# bolid-iso-motor-control.net
KiCad netlist of a schematic drawn in Altium Designer
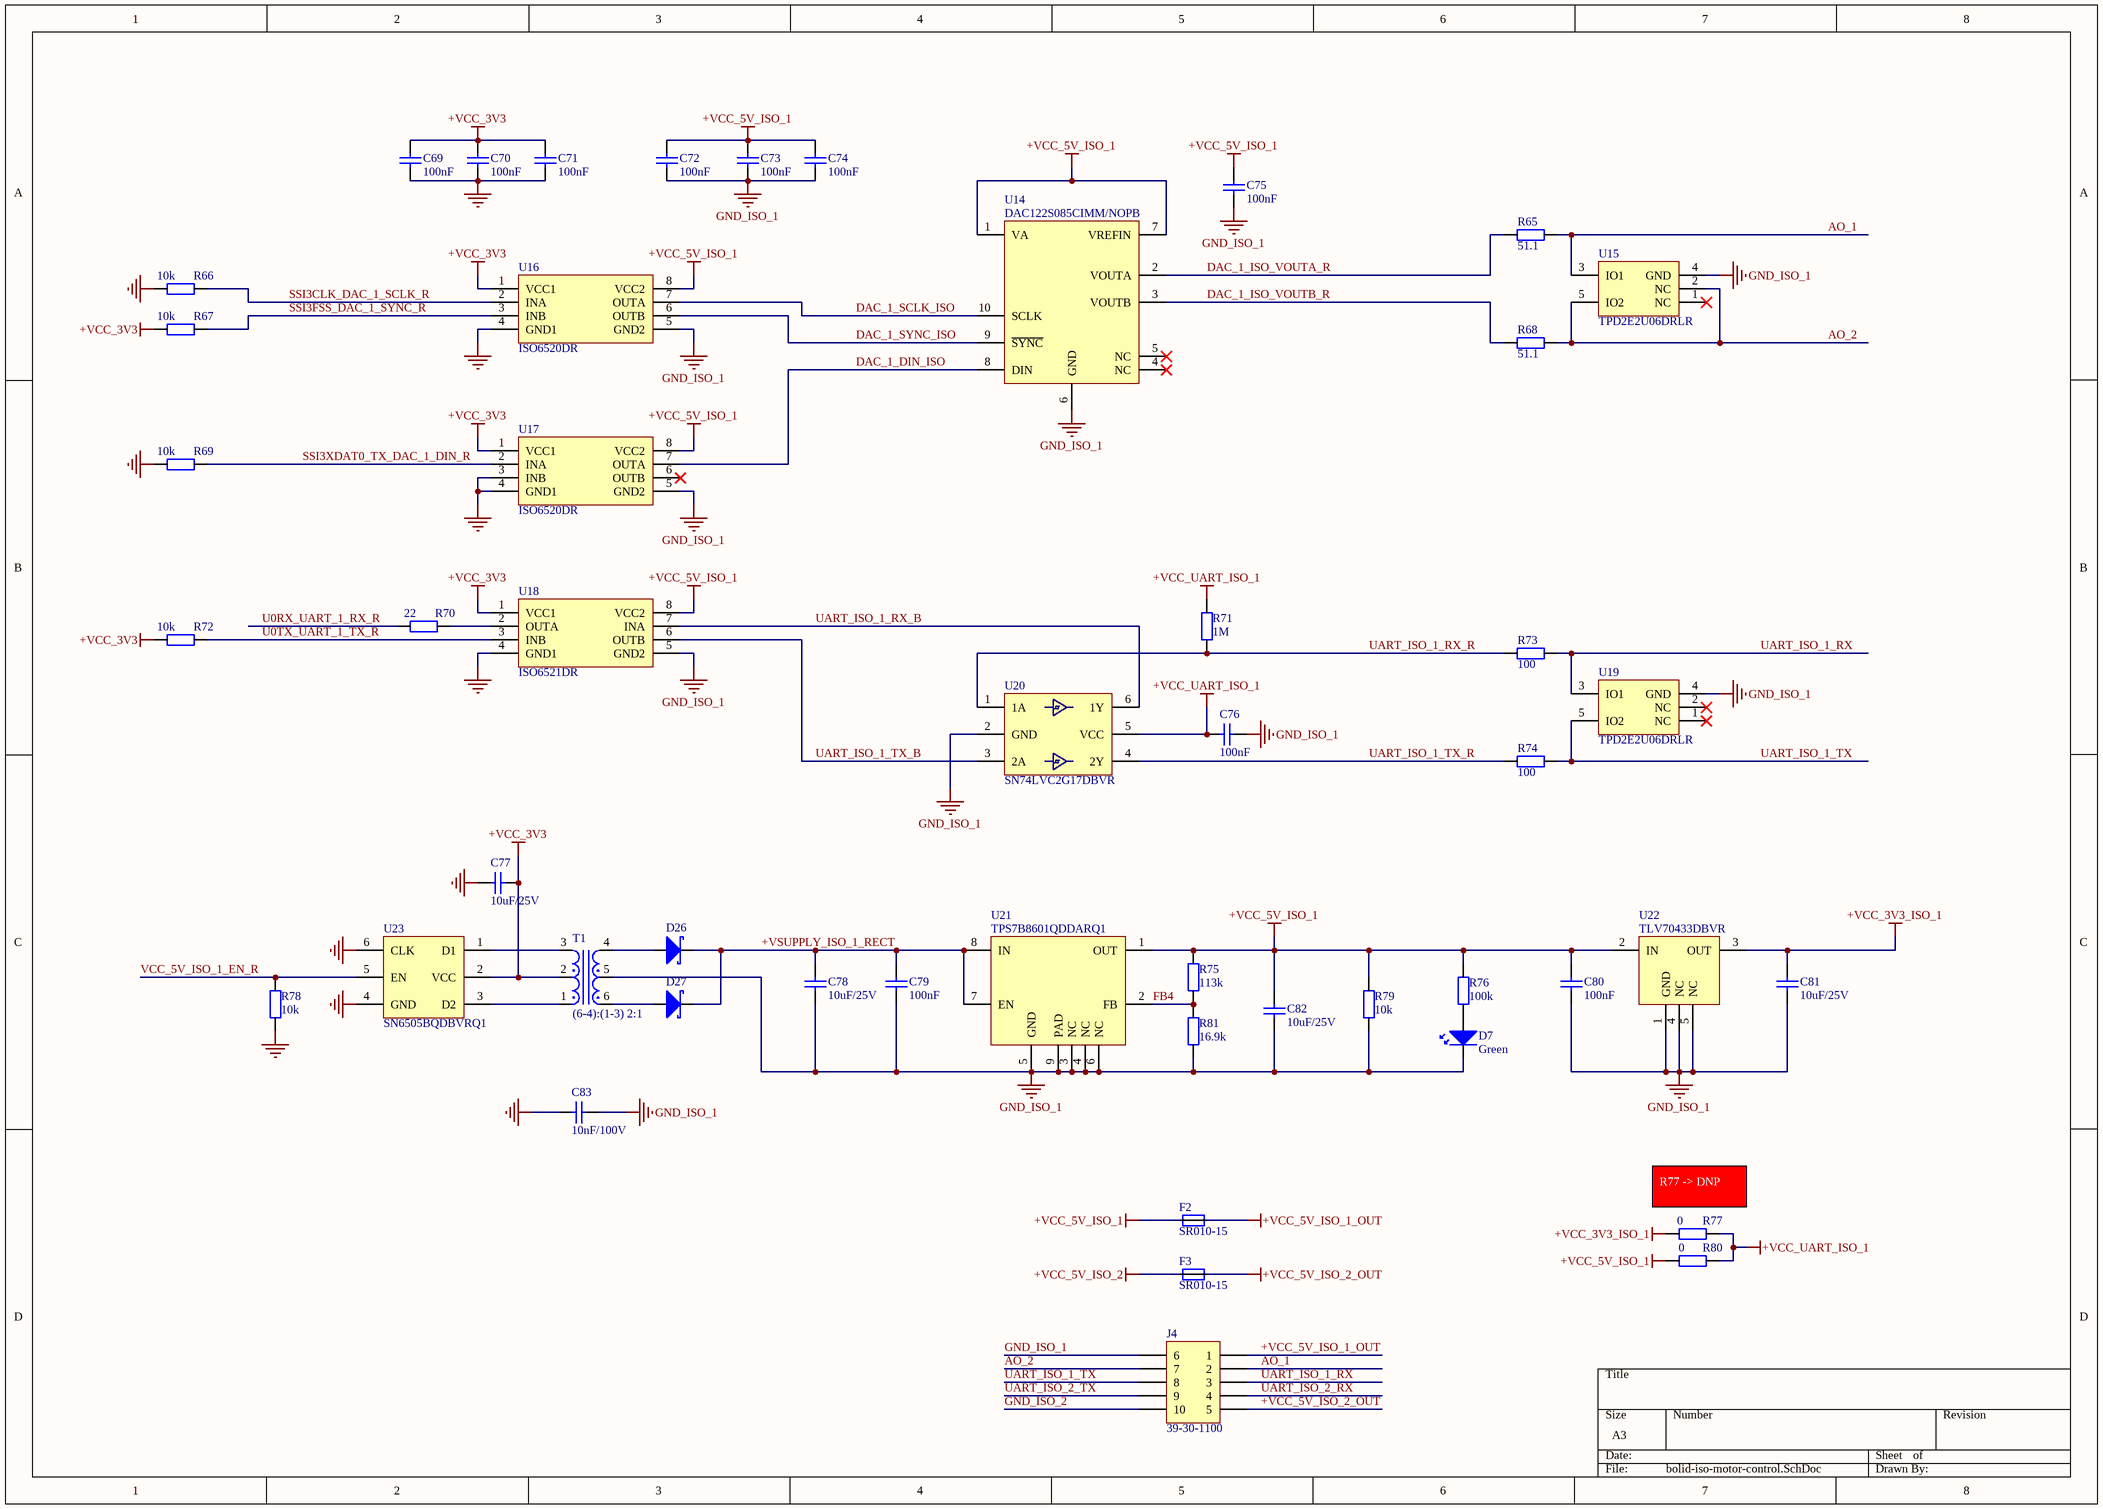
[diagram p0: bolid-iso-motor-control.SchDoc]

(export (version "E")
  (design (tool "Eeschema 10.0.6"))
  (components
    (comp (ref "C69")
      (value "GRM155R71H104KE14D")
      (footprint "C0402-CAPC100X50X55L22 - Tayio Yuden TDK")
      (description "MLCC 0402 (1005) 100nF 10% 50V X7R")
      (fields
        (field (name "MANUFACTURER") "Murata Electronics")
        (field (name "TOLERANCE") "10 %")
        (field (name "VALUE DISPLAYED") "100nF")
      )
      (libsource (lib "capacitors2") (part "GRM155R71H104KE14D"))
    )
    (comp (ref "C70")
      (value "GRM155R71H104KE14D")
      (footprint "C0402-CAPC100X50X55L22 - Tayio Yuden TDK")
      (description "MLCC 0402 (1005) 100nF 10% 50V X7R")
      (fields
        (field (name "MANUFACTURER") "Murata Electronics")
        (field (name "TOLERANCE") "10 %")
        (field (name "VALUE DISPLAYED") "100nF")
      )
      (libsource (lib "capacitors2") (part "GRM155R71H104KE14D"))
    )
    (comp (ref "C71")
      (value "GRM155R71H104KE14D")
      (footprint "C0402-CAPC100X50X55L22 - Tayio Yuden TDK")
      (description "MLCC 0402 (1005) 100nF 10% 50V X7R")
      (fields
        (field (name "MANUFACTURER") "Murata Electronics")
        (field (name "TOLERANCE") "10 %")
        (field (name "VALUE DISPLAYED") "100nF")
      )
      (libsource (lib "capacitors2") (part "GRM155R71H104KE14D"))
    )
    (comp (ref "C72")
      (value "GRM155R71H104KE14D")
      (footprint "C0402-CAPC100X50X55L22 - Tayio Yuden TDK")
      (description "MLCC 0402 (1005) 100nF 10% 50V X7R")
      (fields
        (field (name "MANUFACTURER") "Murata Electronics")
        (field (name "TOLERANCE") "10 %")
        (field (name "VALUE DISPLAYED") "100nF")
      )
      (libsource (lib "capacitors2") (part "GRM155R71H104KE14D"))
    )
    (comp (ref "C73")
      (value "GRM155R71H104KE14D")
      (footprint "C0402-CAPC100X50X55L22 - Tayio Yuden TDK")
      (description "MLCC 0402 (1005) 100nF 10% 50V X7R")
      (fields
        (field (name "MANUFACTURER") "Murata Electronics")
        (field (name "TOLERANCE") "10 %")
        (field (name "VALUE DISPLAYED") "100nF")
      )
      (libsource (lib "capacitors2") (part "GRM155R71H104KE14D"))
    )
    (comp (ref "C74")
      (value "GRM155R71H104KE14D")
      (footprint "C0402-CAPC100X50X55L22 - Tayio Yuden TDK")
      (description "MLCC 0402 (1005) 100nF 10% 50V X7R")
      (fields
        (field (name "MANUFACTURER") "Murata Electronics")
        (field (name "TOLERANCE") "10 %")
        (field (name "VALUE DISPLAYED") "100nF")
      )
      (libsource (lib "capacitors2") (part "GRM155R71H104KE14D"))
    )
    (comp (ref "C75")
      (value "GRM155R71H104KE14D")
      (footprint "C0402-CAPC100X50X55L22 - Tayio Yuden TDK")
      (description "MLCC 0402 (1005) 100nF 10% 50V X7R")
      (fields
        (field (name "MANUFACTURER") "Murata Electronics")
        (field (name "TOLERANCE") "10 %")
        (field (name "VALUE DISPLAYED") "100nF")
      )
      (libsource (lib "capacitors2") (part "GRM155R71H104KE14D"))
    )
    (comp (ref "C76")
      (value "GRM155R71H104KE14D")
      (footprint "C0402-CAPC100X50X55L22 - Tayio Yuden TDK")
      (description "MLCC 0402 (1005) 100nF 10% 50V X7R")
      (fields
        (field (name "MANUFACTURER") "Murata Electronics")
        (field (name "TOLERANCE") "10 %")
        (field (name "VALUE DISPLAYED") "100nF")
      )
      (libsource (lib "capacitors2") (part "GRM155R71H104KE14D"))
    )
    (comp (ref "C77")
      (value "TMK316AB7106KL-T")
      (footprint "C1206-CAPC320X160X190L65N - Murata")
      (description "MLCC 1206 (3216) 10uF 10% 25V X7R")
      (fields
        (field (name "MANUFACTURER") "Taiyo Yuden")
        (field (name "TOLERANCE") "10 %")
        (field (name "VALUE DISPLAYED") "10uF/25V")
      )
      (libsource (lib "capacitors2") (part "TMK316AB7106KL-T"))
    )
    (comp (ref "C78")
      (value "TMK316AB7106KL-T")
      (footprint "C1206-CAPC320X160X190L65N - Murata")
      (description "MLCC 1206 (3216) 10uF 10% 25V X7R")
      (fields
        (field (name "MANUFACTURER") "Taiyo Yuden")
        (field (name "TOLERANCE") "10 %")
        (field (name "VALUE DISPLAYED") "10uF/25V")
      )
      (libsource (lib "capacitors2") (part "TMK316AB7106KL-T"))
    )
    (comp (ref "C79")
      (value "GRM155R71H104KE14D")
      (footprint "C0402-CAPC100X50X55L22 - Tayio Yuden TDK")
      (description "MLCC 0402 (1005) 100nF 10% 50V X7R")
      (fields
        (field (name "MANUFACTURER") "Murata Electronics")
        (field (name "TOLERANCE") "10 %")
        (field (name "VALUE DISPLAYED") "100nF")
      )
      (libsource (lib "capacitors2") (part "GRM155R71H104KE14D"))
    )
    (comp (ref "C80")
      (value "GRM155R71H104KE14D")
      (footprint "C0402-CAPC100X50X55L22 - Tayio Yuden TDK")
      (description "MLCC 0402 (1005) 100nF 10% 50V X7R")
      (fields
        (field (name "MANUFACTURER") "Murata Electronics")
        (field (name "TOLERANCE") "10 %")
        (field (name "VALUE DISPLAYED") "100nF")
      )
      (libsource (lib "capacitors2") (part "GRM155R71H104KE14D"))
    )
    (comp (ref "C81")
      (value "TMK316AB7106KL-T")
      (footprint "C1206-CAPC320X160X190L65N - Murata")
      (description "MLCC 1206 (3216) 10uF 10% 25V X7R")
      (fields
        (field (name "MANUFACTURER") "Taiyo Yuden")
        (field (name "TOLERANCE") "10 %")
        (field (name "VALUE DISPLAYED") "10uF/25V")
      )
      (libsource (lib "capacitors2") (part "TMK316AB7106KL-T"))
    )
    (comp (ref "C82")
      (value "TMK316AB7106KL-T")
      (footprint "C1206-CAPC320X160X190L65N - Murata")
      (description "MLCC 1206 (3216) 10uF 10% 25V X7R")
      (fields
        (field (name "MANUFACTURER") "Taiyo Yuden")
        (field (name "TOLERANCE") "10 %")
        (field (name "VALUE DISPLAYED") "10uF/25V")
      )
      (libsource (lib "capacitors2") (part "TMK316AB7106KL-T"))
    )
    (comp (ref "C83")
      (value "GRM188R72A103KA01J")
      (footprint "C0603-CAPC162X80X95L35N")
      (description "MLCC 0603 (1608) 10nF 10% 100V X7R")
      (fields
        (field (name "MANUFACTURER") "Murata Electronics")
        (field (name "TOLERANCE") "10 %")
        (field (name "VALUE DISPLAYED") "10nF/100V")
      )
      (libsource (lib "capacitors2") (part "GRM188R72A103KA01J"))
    )
    (comp (ref "D7")
      (value "150060GS75000")
      (footprint "D0603 DIONC166X84X36L42N Littelfuse")
      (description "LED 0603 (1608) Green")
      (fields (field (name "MANUFACTURER") "Wurth Elektronik") (field (name "ILLUMINATION COLOR") "Green"))
      (libsource (lib "semiconductors2") (part "150060GS75000"))
    )
    (comp (ref "D26")
      (value "MBR0530T3G")
      (footprint "SOD-123-2L SOD375X160X128L32X60N - Fairchild")
      (description "ON Semi MBR0530T3G; SMT Schottky Diode; 30V 500mA; 2-Pin SOD-123")
      (fields (field (name "MANUFACTURER") "ON Semiconductor"))
      (libsource (lib "semiconductors2") (part "MBR0530T3G"))
    )
    (comp (ref "D27")
      (value "MBR0530T3G")
      (footprint "SOD-123-2L SOD375X160X128L32X60N - Fairchild")
      (description "ON Semi MBR0530T3G; SMT Schottky Diode; 30V 500mA; 2-Pin SOD-123")
      (fields (field (name "MANUFACTURER") "ON Semiconductor"))
      (libsource (lib "semiconductors2") (part "MBR0530T3G"))
    )
    (comp (ref "F2")
      (value "SR010-15")
      (footprint "RESC2214X10N - SR010-15")
      (description "PTC Fuse Hold Current 0.10A, Trip Current 0.30A VMax 15V")
      (fields (field (name "MANUFACTURER") "Excel Cell"))
      (libsource (lib "misc2") (part "SR010-15"))
    )
    (comp (ref "F3")
      (value "SR010-15")
      (footprint "RESC2214X10N - SR010-15")
      (description "PTC Fuse Hold Current 0.10A, Trip Current 0.30A VMax 15V")
      (fields (field (name "MANUFACTURER") "Excel Cell"))
      (libsource (lib "misc2") (part "SR010-15"))
    )
    (comp (ref "J4")
      (value "39-30-1100")
      (footprint "MOLEX Mini-Fit Jr 039301100 2x5 PEG")
      (fields (field (name "MANUFACTURER") "Molex"))
      (libsource (lib "connectors2") (part "039301100"))
    )
    (comp (ref "R65")
      (value "51.1")
      (footprint "R0402-RESC100X50X40L22N")
      (description "RES 0402 (1005) 51.1 ohm 1% 0.0625W 50V Thick Film")
      (fields
        (field (name "MANUFACTURER") "Yageo")
        (field (name "MANUFACTURER PART NUMBER") "AC0402FR-0751R1L")
      )
      (libsource (lib "resistors2") (part "AC0402FR-0751R1L"))
    )
    (comp (ref "R66")
      (value "10k")
      (footprint "R0402-RESC100X50X40L22N")
      (description "RES 0402 (1005) 10.0k 1% 0.0625W 50V Thick Film")
      (fields
        (field (name "MANUFACTURER") "Yageo")
        (field (name "MANUFACTURER PART NUMBER") "RC0402FR-0710KL")
      )
      (libsource (lib "resistors2") (part "RC0402FR-0710KL"))
    )
    (comp (ref "R67")
      (value "10k")
      (footprint "R0402-RESC100X50X40L22N")
      (description "RES 0402 (1005) 10.0k 1% 0.0625W 50V Thick Film")
      (fields
        (field (name "MANUFACTURER") "Yageo")
        (field (name "MANUFACTURER PART NUMBER") "RC0402FR-0710KL")
      )
      (libsource (lib "resistors2") (part "RC0402FR-0710KL"))
    )
    (comp (ref "R68")
      (value "51.1")
      (footprint "R0402-RESC100X50X40L22N")
      (description "RES 0402 (1005) 51.1 ohm 1% 0.0625W 50V Thick Film")
      (fields
        (field (name "MANUFACTURER") "Yageo")
        (field (name "MANUFACTURER PART NUMBER") "AC0402FR-0751R1L")
      )
      (libsource (lib "resistors2") (part "AC0402FR-0751R1L"))
    )
    (comp (ref "R69")
      (value "10k")
      (footprint "R0402-RESC100X50X40L22N")
      (description "RES 0402 (1005) 10.0k 1% 0.0625W 50V Thick Film")
      (fields
        (field (name "MANUFACTURER") "Yageo")
        (field (name "MANUFACTURER PART NUMBER") "RC0402FR-0710KL")
      )
      (libsource (lib "resistors2") (part "RC0402FR-0710KL"))
    )
    (comp (ref "R70")
      (value "22")
      (footprint "R0402-RESC100X50X40L22N")
      (description "RES 0402 (1005) 22.0 ohm 1% 0.0625W 50V Thick Film")
      (fields
        (field (name "MANUFACTURER") "Yageo")
        (field (name "MANUFACTURER PART NUMBER") "RC0402FR-1322RL")
      )
      (libsource (lib "resistors2") (part "RC0402FR-1322RL"))
    )
    (comp (ref "R71")
      (value "1M")
      (footprint "R0402-RESC100X50X40L22N")
      (description "RES 0402 (1005) 1.00M 1% 0.0625W 50V Thick Film")
      (fields
        (field (name "MANUFACTURER") "YAGEO")
        (field (name "MANUFACTURER PART NUMBER") "AC0402FR-071ML")
      )
      (libsource (lib "resistors2") (part "AC0402FR-071ML"))
    )
    (comp (ref "R72")
      (value "10k")
      (footprint "R0402-RESC100X50X40L22N")
      (description "RES 0402 (1005) 10.0k 1% 0.0625W 50V Thick Film")
      (fields
        (field (name "MANUFACTURER") "Yageo")
        (field (name "MANUFACTURER PART NUMBER") "RC0402FR-0710KL")
      )
      (libsource (lib "resistors2") (part "RC0402FR-0710KL"))
    )
    (comp (ref "R73")
      (value "100")
      (footprint "R0402-RESC100X50X40L22N")
      (description "RES 0402 (1005) 100.0 ohm 1% 0.0625W 50V Thick Film")
      (fields
        (field (name "MANUFACTURER") "Yageo")
        (field (name "MANUFACTURER PART NUMBER") "RC0402FR-07100RL")
      )
      (libsource (lib "resistors2") (part "RC0402FR-07100RL"))
    )
    (comp (ref "R74")
      (value "100")
      (footprint "R0402-RESC100X50X40L22N")
      (description "RES 0402 (1005) 100.0 ohm 1% 0.0625W 50V Thick Film")
      (fields
        (field (name "MANUFACTURER") "Yageo")
        (field (name "MANUFACTURER PART NUMBER") "RC0402FR-07100RL")
      )
      (libsource (lib "resistors2") (part "RC0402FR-07100RL"))
    )
    (comp (ref "R75")
      (value "113k")
      (footprint "R0402-RESC100X50X40L22N")
      (description "RES 0402 (1005) 113.0k 1% 0.0625W 50V Thick Film")
      (fields
        (field (name "MANUFACTURER") "Yageo")
        (field (name "MANUFACTURER PART NUMBER") "RC0402FR-07113KL")
      )
      (libsource (lib "resistors2") (part "RC0402FR-07113KL"))
    )
    (comp (ref "R76")
      (value "100k")
      (footprint "R0402-RESC100X50X40L22N")
      (description "RES 0402 (1005) 100.0k 1% 0.0625W 50V Thick Film")
      (fields
        (field (name "MANUFACTURER") "Yageo")
        (field (name "MANUFACTURER PART NUMBER") "RC0402FR-07100KL")
      )
      (libsource (lib "resistors2") (part "RC0402FR-07100KL"))
    )
    (comp (ref "R77")
      (value "0")
      (footprint "R0402-RESC100X50X40L22N")
      (description "RES 0402 (1005) 0.00 ohm 1% 0.0625W 50V Thick Film")
      (fields
        (field (name "MANUFACTURER") "Yageo")
        (field (name "MANUFACTURER PART NUMBER") "RC0402JR-7D0RL")
      )
      (libsource (lib "resistors2") (part "RC0402JR-7D0RL"))
    )
    (comp (ref "R78")
      (value "10k")
      (footprint "R0402-RESC100X50X40L22N")
      (description "RES 0402 (1005) 10.0k 1% 0.0625W 50V Thick Film")
      (fields
        (field (name "MANUFACTURER") "Yageo")
        (field (name "MANUFACTURER PART NUMBER") "RC0402FR-0710KL")
      )
      (libsource (lib "") (part "RC0402FR-0710KL_1"))
    )
    (comp (ref "R79")
      (value "10k")
      (footprint "R0402-RESC100X50X40L22N")
      (description "RES 0402 (1005) 10.0k 1% 0.0625W 50V Thick Film")
      (fields
        (field (name "MANUFACTURER") "Yageo")
        (field (name "MANUFACTURER PART NUMBER") "RC0402FR-0710KL")
      )
      (libsource (lib "") (part "RC0402FR-0710KL_1"))
    )
    (comp (ref "R80")
      (value "0")
      (footprint "R0402-RESC100X50X40L22N")
      (description "RES 0402 (1005) 0.00 ohm 1% 0.0625W 50V Thick Film")
      (fields
        (field (name "MANUFACTURER") "Yageo")
        (field (name "MANUFACTURER PART NUMBER") "RC0402JR-7D0RL")
      )
      (libsource (lib "resistors2") (part "RC0402JR-7D0RL"))
    )
    (comp (ref "R81")
      (value "16.9k")
      (footprint "R0402-RESC100X50X40L22N")
      (description "RES 0402 (1005) 16.9k 1% 0.0625W 50V Thick Film")
      (fields
        (field (name "MANUFACTURER") "Yageo")
        (field (name "MANUFACTURER PART NUMBER") "RC0402FR-0716K9L")
      )
      (libsource (lib "resistors2") (part "RC0402FR-0716K9L"))
    )
    (comp (ref "T1")
      (value "(6-4):(1-3) 2:1")
      (footprint "WE 760390014")
      (description "Transformer 2:1 11VuS 150mAAC Power Transformers MID-SN6501 TI Driver Toroid .475mH 3.3VDC")
      (fields
        (field (name "MANUFACTURER") "Wurth Elektronik / Midcom")
        (field (name "MANUFACTURER PART NUMBER") "760390015")
      )
      (libsource (lib "inductors2") (part "760390015"))
    )
    (comp (ref "U14")
      (value "DAC122S085CIMM/NOPB")
      (footprint "TI VSSOP10 DGS0010A TSSOP50P490X110-10N")
      (description "12-Bit Micro Power DUAL Digital-to-Analog Converter with ail-to- ail Output 10-VSSOP -40 to 105")
      (fields (field (name "MANUFACTURER") "TI National Semiconductor"))
      (libsource (lib "ics2") (part "DAC122S085CIMM/NOPB"))
    )
    (comp (ref "U15")
      (value "TPD2E2U06DRLR")
      (footprint "TI SOT-5X3 DRL0005A SOTFL50P160X60-5N")
      (description "TVS DIODE 5.5VWM 12.4VC 5SOT")
      (fields (field (name "MANUFACTURER") "Texas Instruments"))
      (libsource (lib "semiconductors2") (part "TPD2E2U06DRLR"))
    )
    (comp (ref "U16")
      (value "ISO6520DR")
      (footprint "TI SOIC8 D0008A SOIC8P127_490X599X175L84X41N")
      (description "Functional isolation dual-channel 2/0 digital isolator 8-SOIC -40 to 125")
      (fields (field (name "MANUFACTURER") "Texas Instruments"))
      (libsource (lib "ics2") (part "ISO6520DR"))
    )
    (comp (ref "U17")
      (value "ISO6520DR")
      (footprint "TI SOIC8 D0008A SOIC8P127_490X599X175L84X41N")
      (description "Functional isolation dual-channel 2/0 digital isolator 8-SOIC -40 to 125")
      (fields (field (name "MANUFACTURER") "Texas Instruments"))
      (libsource (lib "ics2") (part "ISO6520DR"))
    )
    (comp (ref "U18")
      (value "ISO6521DR")
      (footprint "TI SOIC8 D0008A SOIC8P127_490X599X175L84X41N")
      (description "Functional isolation dual-channel 1/1 digital isolator 8-SOIC -40 to 125")
      (fields (field (name "MANUFACTURER") "Texas Instruments"))
      (libsource (lib "ics2") (part "ISO6521DR"))
    )
    (comp (ref "U19")
      (value "TPD2E2U06DRLR")
      (footprint "TI SOT-5X3 DRL0005A SOTFL50P160X60-5N")
      (description "TVS DIODE 5.5VWM 12.4VC 5SOT")
      (fields (field (name "MANUFACTURER") "Texas Instruments"))
      (libsource (lib "semiconductors2") (part "TPD2E2U06DRLR"))
    )
    (comp (ref "U20")
      (value "SN74LVC2G17DBVR")
      (footprint "TI SOT23 DBV0006A SOT23-6P95_280X145L45X37N")
      (description "2-ch, 1.65-V to 5.5-V buffers with Schmitt-Trigger inputs 6-SOT-23 -40 to 125")
      (fields (field (name "MANUFACTURER") "Texas Instruments"))
      (libsource (lib "ics2") (part "SN74LVC2G17DBVR"))
    )
    (comp (ref "U21")
      (value "TPS7B8601QDDARQ1")
      (footprint "TI SOIC8 DDA0008E-C01 SOIC127P600X170_HS-9N")
      (fields (field (name "MANUFACTURER") "Texas Instruments"))
      (libsource (lib "ics2") (part "TPS7B8601QDDARQ1"))
    )
    (comp (ref "U22")
      (value "TLV70433DBVR")
      (footprint "TI SOT23 DBV0005A SOT23-5P95_280X145L45X40N")
      (description "IC REG LDO 3.3V 0.15A SOT23-5")
      (fields (field (name "MANUFACTURER") "Texas Instruments"))
      (libsource (lib "ics2") (part "TLV70433DBVR"))
    )
    (comp (ref "U23")
      (value "SN6505BQDBVRQ1")
      (footprint "TI SOT23 DBV0006A SOT23-6P95_280X145L45X37N")
      (description "Power Management Specialized - PMIC A 595-SN6505BQDBVTQ1")
      (fields (field (name "MANUFACTURER") "Texas Instruments"))
      (libsource (lib "ics2") (part "SN6505BQDBVRQ1"))
    )
  )
  (nets
    (net (code "1") (name "+VCC_3V3") (class "Default")
      (node (ref "C69") (pin "2") (pinfunction "2_2") (pintype "passive"))
      (node (ref "C70") (pin "2") (pinfunction "2_2") (pintype "passive"))
      (node (ref "C71") (pin "2") (pinfunction "2_2") (pintype "passive"))
      (node (ref "C77") (pin "2") (pinfunction "2_2") (pintype "passive"))
      (node (ref "R67") (pin "2") (pinfunction "2_2") (pintype "passive"))
      (node (ref "R72") (pin "2") (pinfunction "2_2") (pintype "passive"))
      (node (ref "T1") (pin "2") (pinfunction "2_2") (pintype "passive"))
      (node (ref "U16") (pin "1") (pinfunction "VCC1_1") (pintype "passive"))
      (node (ref "U17") (pin "1") (pinfunction "VCC1_1") (pintype "passive"))
      (node (ref "U18") (pin "1") (pinfunction "VCC1_1") (pintype "passive"))
      (node (ref "U23") (pin "2") (pinfunction "VCC_2") (pintype "passive"))
    )
    (net (code "2") (name "+VCC_3V3_ISO_1") (class "Default")
      (node (ref "C81") (pin "2") (pinfunction "2_2") (pintype "passive"))
      (node (ref "R77") (pin "1") (pinfunction "1_1") (pintype "passive"))
      (node (ref "U22") (pin "3") (pinfunction "OUT_3") (pintype "passive"))
    )
    (net (code "3") (name "+VCC_5V_ISO_1") (class "Default")
      (node (ref "C72") (pin "2") (pinfunction "2_2") (pintype "passive"))
      (node (ref "C73") (pin "2") (pinfunction "2_2") (pintype "passive"))
      (node (ref "C74") (pin "2") (pinfunction "2_2") (pintype "passive"))
      (node (ref "C75") (pin "2") (pinfunction "2_2") (pintype "passive"))
      (node (ref "C80") (pin "2") (pinfunction "2_2") (pintype "passive"))
      (node (ref "C82") (pin "2") (pinfunction "2_2") (pintype "passive"))
      (node (ref "F2") (pin "1") (pinfunction "1_1") (pintype "passive"))
      (node (ref "R75") (pin "2") (pinfunction "2_2") (pintype "passive"))
      (node (ref "R76") (pin "2") (pinfunction "2_2") (pintype "passive"))
      (node (ref "R79") (pin "2") (pinfunction "2_2") (pintype "passive"))
      (node (ref "R80") (pin "1") (pinfunction "1_1") (pintype "passive"))
      (node (ref "U14") (pin "1") (pinfunction "VA_1") (pintype "passive"))
      (node (ref "U14") (pin "7") (pinfunction "VREFIN_7") (pintype "passive"))
      (node (ref "U16") (pin "8") (pinfunction "VCC2_8") (pintype "passive"))
      (node (ref "U17") (pin "8") (pinfunction "VCC2_8") (pintype "passive"))
      (node (ref "U18") (pin "8") (pinfunction "VCC2_8") (pintype "passive"))
      (node (ref "U21") (pin "1") (pinfunction "OUT_1") (pintype "passive"))
      (node (ref "U22") (pin "2") (pinfunction "IN_2") (pintype "passive"))
    )
    (net (code "4") (name "+VCC_5V_ISO_1_OUT") (class "Default")
      (node (ref "F2") (pin "2") (pinfunction "2_2") (pintype "passive"))
      (node (ref "J4") (pin "1") (pinfunction "1_1") (pintype "passive"))
    )
    (net (code "5") (name "+VCC_5V_ISO_2") (class "Default")
      (node (ref "F3") (pin "1") (pinfunction "1_1") (pintype "passive"))
    )
    (net (code "6") (name "+VCC_5V_ISO_2_OUT") (class "Default")
      (node (ref "F3") (pin "2") (pinfunction "2_2") (pintype "passive"))
      (node (ref "J4") (pin "5") (pinfunction "5_5") (pintype "passive"))
    )
    (net (code "7") (name "+VCC_UART_ISO_1") (class "Default")
      (node (ref "C76") (pin "2") (pinfunction "2_2") (pintype "passive"))
      (node (ref "R71") (pin "2") (pinfunction "2_2") (pintype "passive"))
      (node (ref "R77") (pin "2") (pinfunction "2_2") (pintype "passive"))
      (node (ref "R80") (pin "2") (pinfunction "2_2") (pintype "passive"))
      (node (ref "U20") (pin "5") (pinfunction "VCC_5") (pintype "passive"))
    )
    (net (code "8") (name "/+VSUPPLY_ISO_1_RECT") (class "Default")
      (node (ref "C78") (pin "2") (pinfunction "2_2") (pintype "passive"))
      (node (ref "C79") (pin "2") (pinfunction "2_2") (pintype "passive"))
      (node (ref "D26") (pin "1") (pinfunction "K_1") (pintype "passive"))
      (node (ref "D27") (pin "1") (pinfunction "K_1") (pintype "passive"))
      (node (ref "U21") (pin "7") (pinfunction "EN_7") (pintype "passive"))
      (node (ref "U21") (pin "8") (pinfunction "IN_8") (pintype "passive"))
    )
    (net (code "9") (name "/AO_1") (class "Default")
      (node (ref "J4") (pin "2") (pinfunction "2_2") (pintype "passive"))
      (node (ref "R65") (pin "2") (pinfunction "2_2") (pintype "passive"))
      (node (ref "U15") (pin "3") (pinfunction "IO1_3") (pintype "passive"))
    )
    (net (code "10") (name "/AO_2") (class "Default")
      (node (ref "J4") (pin "7") (pinfunction "7_7") (pintype "passive"))
      (node (ref "R68") (pin "2") (pinfunction "2_2") (pintype "passive"))
      (node (ref "U15") (pin "2") (pinfunction "NC_2") (pintype "passive"))
      (node (ref "U15") (pin "5") (pinfunction "IO2_5") (pintype "passive"))
    )
    (net (code "11") (name "/DAC_1_DIN_ISO") (class "Default")
      (node (ref "U14") (pin "8") (pinfunction "DIN_8") (pintype "passive"))
      (node (ref "U17") (pin "7") (pinfunction "OUTA_7") (pintype "passive"))
    )
    (net (code "12") (name "/DAC_1_ISO_VOUTA_R") (class "Default")
      (node (ref "R65") (pin "1") (pinfunction "1_1") (pintype "passive"))
      (node (ref "U14") (pin "2") (pinfunction "VOUTA_2") (pintype "passive"))
    )
    (net (code "13") (name "/DAC_1_ISO_VOUTB_R") (class "Default")
      (node (ref "R68") (pin "1") (pinfunction "1_1") (pintype "passive"))
      (node (ref "U14") (pin "3") (pinfunction "VOUTB_3") (pintype "passive"))
    )
    (net (code "14") (name "/DAC_1_SCLK_ISO") (class "Default")
      (node (ref "U14") (pin "10") (pinfunction "SCLK_10") (pintype "passive"))
      (node (ref "U16") (pin "7") (pinfunction "OUTA_7") (pintype "passive"))
    )
    (net (code "15") (name "/DAC_1_SYNC_ISO") (class "Default")
      (node (ref "U14") (pin "9") (pinfunction "~{SYNC}_9") (pintype "passive"))
      (node (ref "U16") (pin "6") (pinfunction "OUTB_6") (pintype "passive"))
    )
    (net (code "16") (name "/FB4") (class "Default")
      (node (ref "R75") (pin "1") (pinfunction "1_1") (pintype "passive"))
      (node (ref "R81") (pin "2") (pinfunction "2_2") (pintype "passive"))
      (node (ref "U21") (pin "2") (pinfunction "FB_2") (pintype "passive"))
    )
    (net (code "17") (name "/GND_ISO_2") (class "Default")
      (node (ref "J4") (pin "10") (pinfunction "10_10") (pintype "passive"))
    )
    (net (code "18") (name "/SSI3CLK_DAC_1_SCLK_R") (class "Default")
      (node (ref "R66") (pin "1") (pinfunction "1_1") (pintype "passive"))
      (node (ref "U16") (pin "2") (pinfunction "INA_2") (pintype "passive"))
    )
    (net (code "19") (name "/SSI3FSS_DAC_1_SYNC_R") (class "Default")
      (node (ref "R67") (pin "1") (pinfunction "1_1") (pintype "passive"))
      (node (ref "U16") (pin "3") (pinfunction "INB_3") (pintype "passive"))
    )
    (net (code "20") (name "/SSI3XDAT0_TX_DAC_1_DIN_R") (class "Default")
      (node (ref "R69") (pin "1") (pinfunction "1_1") (pintype "passive"))
      (node (ref "U17") (pin "2") (pinfunction "INA_2") (pintype "passive"))
    )
    (net (code "21") (name "/U0RX_UART_1_RX_R") (class "Default")
      (node (ref "R70") (pin "1") (pinfunction "1_1") (pintype "passive"))
    )
    (net (code "22") (name "/U0TX_UART_1_TX_R") (class "Default")
      (node (ref "R72") (pin "1") (pinfunction "1_1") (pintype "passive"))
      (node (ref "U18") (pin "3") (pinfunction "INB_3") (pintype "passive"))
    )
    (net (code "23") (name "/UART_ISO_1_RX") (class "Default")
      (node (ref "J4") (pin "3") (pinfunction "3_3") (pintype "passive"))
      (node (ref "R73") (pin "2") (pinfunction "2_2") (pintype "passive"))
      (node (ref "U19") (pin "3") (pinfunction "IO1_3") (pintype "passive"))
    )
    (net (code "24") (name "/UART_ISO_1_RX_B") (class "Default")
      (node (ref "U18") (pin "7") (pinfunction "INA_7") (pintype "passive"))
      (node (ref "U20") (pin "6") (pinfunction "1Y_6") (pintype "passive"))
    )
    (net (code "25") (name "/UART_ISO_1_RX_R") (class "Default")
      (node (ref "R71") (pin "1") (pinfunction "1_1") (pintype "passive"))
      (node (ref "R73") (pin "1") (pinfunction "1_1") (pintype "passive"))
      (node (ref "U20") (pin "1") (pinfunction "1A_1") (pintype "passive"))
    )
    (net (code "26") (name "/UART_ISO_1_TX") (class "Default")
      (node (ref "J4") (pin "8") (pinfunction "8_8") (pintype "passive"))
      (node (ref "R74") (pin "2") (pinfunction "2_2") (pintype "passive"))
      (node (ref "U19") (pin "5") (pinfunction "IO2_5") (pintype "passive"))
    )
    (net (code "27") (name "/UART_ISO_1_TX_B") (class "Default")
      (node (ref "U18") (pin "6") (pinfunction "OUTB_6") (pintype "passive"))
      (node (ref "U20") (pin "3") (pinfunction "2A_3") (pintype "passive"))
    )
    (net (code "28") (name "/UART_ISO_1_TX_R") (class "Default")
      (node (ref "R74") (pin "1") (pinfunction "1_1") (pintype "passive"))
      (node (ref "U20") (pin "4") (pinfunction "2Y_4") (pintype "passive"))
    )
    (net (code "29") (name "/UART_ISO_2_RX") (class "Default")
      (node (ref "J4") (pin "4") (pinfunction "4_4") (pintype "passive"))
    )
    (net (code "30") (name "/UART_ISO_2_TX") (class "Default")
      (node (ref "J4") (pin "9") (pinfunction "9_9") (pintype "passive"))
    )
    (net (code "31") (name "/VCC_5V_ISO_1_EN_R") (class "Default")
      (node (ref "R78") (pin "2") (pinfunction "2_2") (pintype "passive"))
      (node (ref "U23") (pin "5") (pinfunction "EN_5") (pintype "passive"))
    )
    (net (code "32") (name "GND") (class "Default")
      (node (ref "C69") (pin "1") (pinfunction "1_1") (pintype "passive"))
      (node (ref "C70") (pin "1") (pinfunction "1_1") (pintype "passive"))
      (node (ref "C71") (pin "1") (pinfunction "1_1") (pintype "passive"))
      (node (ref "C77") (pin "1") (pinfunction "1_1") (pintype "passive"))
      (node (ref "C83") (pin "1") (pinfunction "1_1") (pintype "passive"))
      (node (ref "R66") (pin "2") (pinfunction "2_2") (pintype "passive"))
      (node (ref "R69") (pin "2") (pinfunction "2_2") (pintype "passive"))
      (node (ref "R78") (pin "1") (pinfunction "1_1") (pintype "passive"))
      (node (ref "U16") (pin "4") (pinfunction "GND1_4") (pintype "passive"))
      (node (ref "U17") (pin "3") (pinfunction "INB_3") (pintype "passive"))
      (node (ref "U17") (pin "4") (pinfunction "GND1_4") (pintype "passive"))
      (node (ref "U18") (pin "4") (pinfunction "GND1_4") (pintype "passive"))
      (node (ref "U23") (pin "4") (pinfunction "GND_4") (pintype "passive"))
      (node (ref "U23") (pin "6") (pinfunction "CLK_6") (pintype "passive"))
    )
    (net (code "33") (name "GND_ISO_1") (class "Default")
      (node (ref "C72") (pin "1") (pinfunction "1_1") (pintype "passive"))
      (node (ref "C73") (pin "1") (pinfunction "1_1") (pintype "passive"))
      (node (ref "C74") (pin "1") (pinfunction "1_1") (pintype "passive"))
      (node (ref "C75") (pin "1") (pinfunction "1_1") (pintype "passive"))
      (node (ref "C76") (pin "1") (pinfunction "1_1") (pintype "passive"))
      (node (ref "C78") (pin "1") (pinfunction "1_1") (pintype "passive"))
      (node (ref "C79") (pin "1") (pinfunction "1_1") (pintype "passive"))
      (node (ref "C80") (pin "1") (pinfunction "1_1") (pintype "passive"))
      (node (ref "C81") (pin "1") (pinfunction "1_1") (pintype "passive"))
      (node (ref "C82") (pin "1") (pinfunction "1_1") (pintype "passive"))
      (node (ref "C83") (pin "2") (pinfunction "2_2") (pintype "passive"))
      (node (ref "D7") (pin "1") (pinfunction "K_1") (pintype "passive"))
      (node (ref "J4") (pin "6") (pinfunction "6_6") (pintype "passive"))
      (node (ref "R79") (pin "1") (pinfunction "1_1") (pintype "passive"))
      (node (ref "R81") (pin "1") (pinfunction "1_1") (pintype "passive"))
      (node (ref "T1") (pin "5") (pinfunction "5_5") (pintype "passive"))
      (node (ref "U14") (pin "6") (pinfunction "GND_6") (pintype "passive"))
      (node (ref "U15") (pin "4") (pinfunction "GND_4") (pintype "passive"))
      (node (ref "U16") (pin "5") (pinfunction "GND2_5") (pintype "passive"))
      (node (ref "U17") (pin "5") (pinfunction "GND2_5") (pintype "passive"))
      (node (ref "U18") (pin "5") (pinfunction "GND2_5") (pintype "passive"))
      (node (ref "U19") (pin "4") (pinfunction "GND_4") (pintype "passive"))
      (node (ref "U20") (pin "2") (pinfunction "GND_2") (pintype "passive"))
      (node (ref "U21") (pin "3") (pinfunction "NC_3") (pintype "passive"))
      (node (ref "U21") (pin "4") (pinfunction "NC_4") (pintype "passive"))
      (node (ref "U21") (pin "5") (pinfunction "GND_5") (pintype "passive"))
      (node (ref "U21") (pin "6") (pinfunction "NC_6") (pintype "passive"))
      (node (ref "U21") (pin "9") (pinfunction "PAD_9") (pintype "passive"))
      (node (ref "U22") (pin "1") (pinfunction "GND_1") (pintype "passive"))
      (node (ref "U22") (pin "4") (pinfunction "NC_4") (pintype "passive"))
      (node (ref "U22") (pin "5") (pinfunction "NC_5") (pintype "passive"))
    )
    (net (code "34") (name "Net-(D7-A)") (class "Default")
      (node (ref "D7") (pin "2") (pinfunction "A_2") (pintype "passive"))
      (node (ref "R76") (pin "1") (pinfunction "1_1") (pintype "passive"))
    )
    (net (code "35") (name "Net-(D26-A)") (class "Default")
      (node (ref "D26") (pin "2") (pinfunction "A_2") (pintype "passive"))
      (node (ref "T1") (pin "4") (pinfunction "4_4") (pintype "passive"))
    )
    (net (code "36") (name "Net-(D27-A)") (class "Default")
      (node (ref "D27") (pin "2") (pinfunction "A_2") (pintype "passive"))
      (node (ref "T1") (pin "6") (pinfunction "6_6") (pintype "passive"))
    )
    (net (code "37") (name "Net-(U18-OUTA)") (class "Default")
      (node (ref "R70") (pin "2") (pinfunction "2_2") (pintype "passive"))
      (node (ref "U18") (pin "2") (pinfunction "OUTA_2") (pintype "passive"))
    )
    (net (code "38") (name "Net-(U23-D1)") (class "Default")
      (node (ref "T1") (pin "3") (pinfunction "3_3") (pintype "passive"))
      (node (ref "U23") (pin "1") (pinfunction "D1_1") (pintype "passive"))
    )
    (net (code "39") (name "Net-(U23-D2)") (class "Default")
      (node (ref "T1") (pin "1") (pinfunction "1_1") (pintype "passive"))
      (node (ref "U23") (pin "3") (pinfunction "D2_3") (pintype "passive"))
    )
    (net (code "40") (name "unconnected-(U14-NC-Pad4)") (class "Default")
      (node (ref "U14") (pin "4") (pinfunction "NC_4") (pintype "passive+no_connect"))
    )
    (net (code "41") (name "unconnected-(U14-NC-Pad5)") (class "Default")
      (node (ref "U14") (pin "5") (pinfunction "NC_5") (pintype "passive+no_connect"))
    )
    (net (code "42") (name "unconnected-(U15-NC-Pad1)") (class "Default")
      (node (ref "U15") (pin "1") (pinfunction "NC_1") (pintype "passive+no_connect"))
    )
    (net (code "43") (name "unconnected-(U17-OUTB-Pad6)") (class "Default")
      (node (ref "U17") (pin "6") (pinfunction "OUTB_6") (pintype "passive+no_connect"))
    )
    (net (code "44") (name "unconnected-(U19-NC-Pad1)") (class "Default")
      (node (ref "U19") (pin "1") (pinfunction "NC_1") (pintype "passive+no_connect"))
    )
    (net (code "45") (name "unconnected-(U19-NC-Pad2)") (class "Default")
      (node (ref "U19") (pin "2") (pinfunction "NC_2") (pintype "passive+no_connect"))
    )
  )
)
